# mapleSDuino-V0_1_020-eagle7.net
KiCad netlist of a schematic drawn in EAGLE
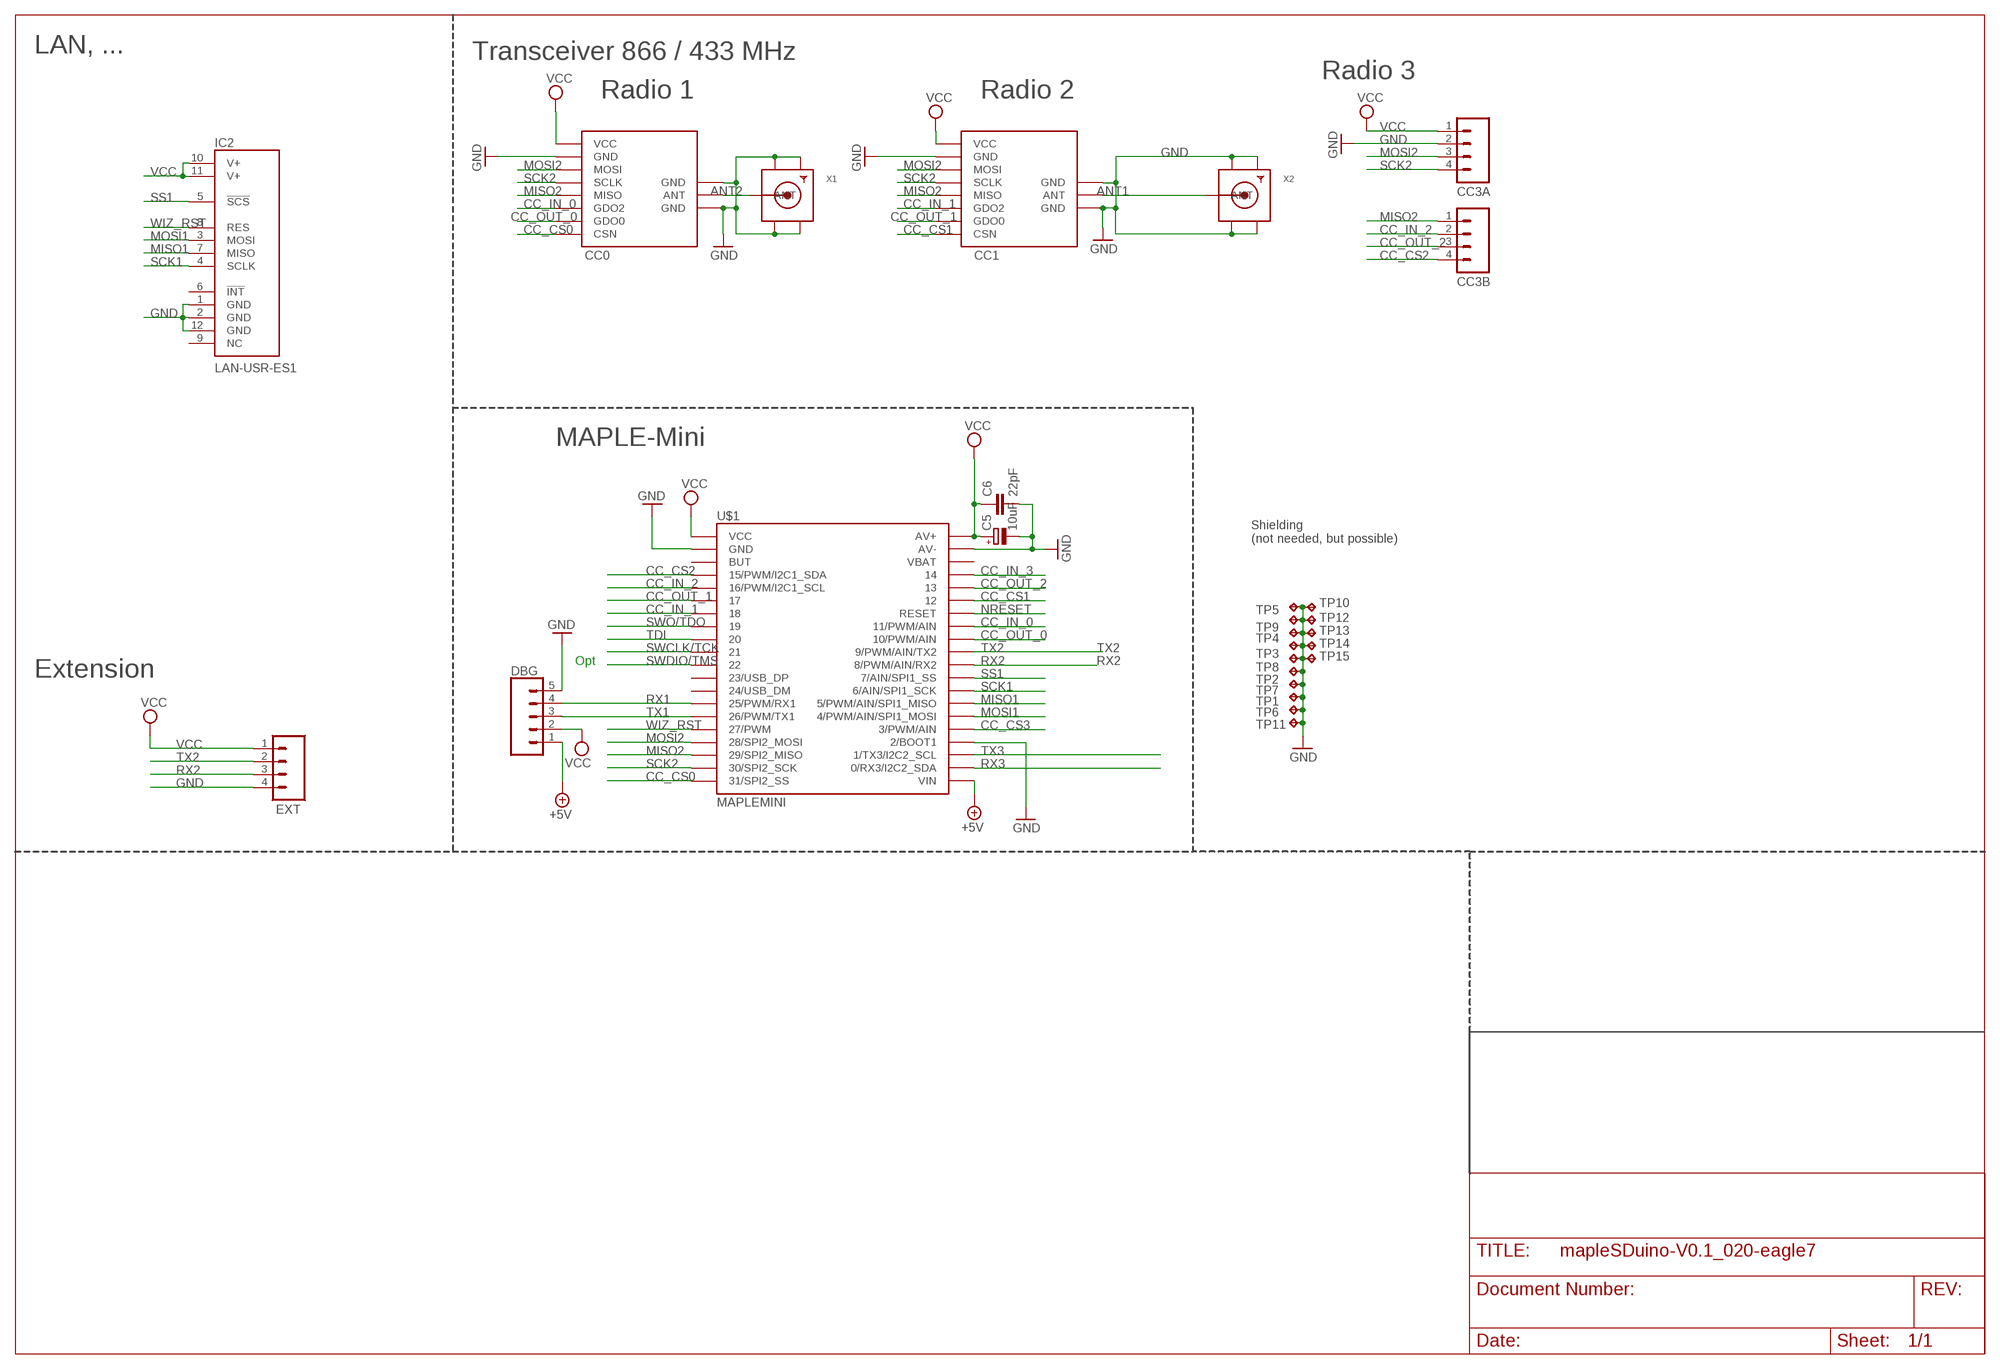
[diagram p0: schematic, sheet 1]

(export (version "E")
  (design (tool "Eeschema 10.0.6"))
  (components
    (comp (ref "C5")
      (value "10uF")
      (footprint "eagle-import:R_2012-12W")
      (libsource (lib "eagle-import") (part "CPOL-EUR/2012-12W"))
    )
    (comp (ref "C6")
      (value "22pF")
      (footprint "eagle-import:C0805")
      (libsource (lib "eagle-import") (part "C-EUC0805"))
    )
    (comp (ref "CC0")
      (value "CC1101")
      (footprint "eagle-import:CC1101_MODULE1_SMD")
      (libsource (lib "eagle-import") (part "CC1101_MODULE1SMD"))
    )
    (comp (ref "CC1")
      (value "CC1101_MODULE1SMD")
      (footprint "eagle-import:CC1101_MODULE1_SMD")
      (libsource (lib "eagle-import") (part "CC1101_MODULE1SMD"))
    )
    (comp (ref "CC3A")
      (value "CONN_04PTH")
      (footprint "eagle-import:1X04")
      (libsource (lib "eagle-import") (part "CONN_04PTH"))
    )
    (comp (ref "CC3B")
      (value "CONN_04PTH")
      (footprint "eagle-import:1X04")
      (libsource (lib "eagle-import") (part "CONN_04PTH"))
    )
    (comp (ref "DBG")
      (value "CONN_05LOCK")
      (footprint "eagle-import:1X05_LOCK")
      (libsource (lib "eagle-import") (part "CONN_05LOCK"))
    )
    (comp (ref "EXT")
      (value "CONN_04PTH")
      (footprint "eagle-import:1X04")
      (libsource (lib "eagle-import") (part "CONN_04PTH"))
    )
    (comp (ref "IC2")
      (value "LAN-USR-ES1")
      (footprint "eagle-import:USR-ES1")
      (libsource (lib "eagle-import") (part "LAN-USR-ES1"))
    )
    (comp (ref "TP1")
      (value "TPTP06SQ")
      (footprint "eagle-import:TP06SQ")
      (libsource (lib "eagle-import") (part "TPTP06SQ"))
    )
    (comp (ref "TP2")
      (value "TPTP06SQ")
      (footprint "eagle-import:TP06SQ")
      (libsource (lib "eagle-import") (part "TPTP06SQ"))
    )
    (comp (ref "TP3")
      (value "TPTP06SQ")
      (footprint "eagle-import:TP06SQ")
      (libsource (lib "eagle-import") (part "TPTP06SQ"))
    )
    (comp (ref "TP4")
      (value "TPTP06SQ")
      (footprint "eagle-import:TP06SQ")
      (libsource (lib "eagle-import") (part "TPTP06SQ"))
    )
    (comp (ref "TP5")
      (value "TPTP06SQ")
      (footprint "eagle-import:TP06SQ")
      (libsource (lib "eagle-import") (part "TPTP06SQ"))
    )
    (comp (ref "TP6")
      (value "TPTP06SQ")
      (footprint "eagle-import:TP06SQ")
      (libsource (lib "eagle-import") (part "TPTP06SQ"))
    )
    (comp (ref "TP7")
      (value "TPTP06SQ")
      (footprint "eagle-import:TP06SQ")
      (libsource (lib "eagle-import") (part "TPTP06SQ"))
    )
    (comp (ref "TP8")
      (value "TPTP06SQ")
      (footprint "eagle-import:TP06SQ")
      (libsource (lib "eagle-import") (part "TPTP06SQ"))
    )
    (comp (ref "TP9")
      (value "TPTP06SQ")
      (footprint "eagle-import:TP06SQ")
      (libsource (lib "eagle-import") (part "TPTP06SQ"))
    )
    (comp (ref "TP10")
      (value "TPTP06SQ")
      (footprint "eagle-import:TP06SQ")
      (libsource (lib "eagle-import") (part "TPTP06SQ"))
    )
    (comp (ref "TP11")
      (value "TPTP06SQ")
      (footprint "eagle-import:TP06SQ")
      (libsource (lib "eagle-import") (part "TPTP06SQ"))
    )
    (comp (ref "TP12")
      (value "TPTP06SQ")
      (footprint "eagle-import:TP06SQ")
      (libsource (lib "eagle-import") (part "TPTP06SQ"))
    )
    (comp (ref "TP13")
      (value "TPTP06SQ")
      (footprint "eagle-import:TP06SQ")
      (libsource (lib "eagle-import") (part "TPTP06SQ"))
    )
    (comp (ref "TP14")
      (value "TPTP06SQ")
      (footprint "eagle-import:TP06SQ")
      (libsource (lib "eagle-import") (part "TPTP06SQ"))
    )
    (comp (ref "TP15")
      (value "TPTP06SQ")
      (footprint "eagle-import:TP06SQ")
      (libsource (lib "eagle-import") (part "TPTP06SQ"))
    )
    (comp (ref "U$1")
      (value "MAPLEMINI")
      (footprint "eagle-import:20-DIP")
      (libsource (lib "eagle-import") (part "MAPLEMINI"))
    )
    (comp (ref "X1")
      (value "SMACONNECTOR_EDGE")
      (footprint "eagle-import:SMA_EDGELAUNCH")
      (libsource (lib "eagle-import") (part "SMACONNECTOR_EDGE"))
    )
    (comp (ref "X2")
      (value "SMACONNECTOR_EDGE")
      (footprint "eagle-import:SMA_EDGELAUNCH")
      (libsource (lib "eagle-import") (part "SMACONNECTOR_EDGE"))
    )
  )
  (nets
    (net (code "1") (name "+5V") (class "Default")
      (node (ref "DBG") (pin "1") (pinfunction "1_1") (pintype "passive"))
      (node (ref "U$1") (pin "21") (pinfunction "VIN_21") (pintype "bidirectional"))
    )
    (net (code "2") (name "/ANT1") (class "Default")
      (node (ref "CC1") (pin "ANT") (pinfunction "ANT_ANT") (pintype "output"))
      (node (ref "X2") (pin "P") (pinfunction "ANT_P") (pintype "bidirectional"))
    )
    (net (code "3") (name "/ANT2") (class "Default")
      (node (ref "CC0") (pin "ANT") (pinfunction "ANT_ANT") (pintype "output"))
      (node (ref "X1") (pin "P") (pinfunction "ANT_P") (pintype "bidirectional"))
    )
    (net (code "4") (name "/CC_CS0") (class "Default")
      (node (ref "CC0") (pin "CSN") (pinfunction "CSN_CSN") (pintype "bidirectional"))
      (node (ref "U$1") (pin "20") (pinfunction "31/SPI2_SS_20") (pintype "bidirectional"))
    )
    (net (code "5") (name "/CC_CS1") (class "Default")
      (node (ref "CC1") (pin "CSN") (pinfunction "CSN_CSN") (pintype "bidirectional"))
      (node (ref "U$1") (pin "35") (pinfunction "12_35") (pintype "bidirectional"))
    )
    (net (code "6") (name "/CC_CS2") (class "Default")
      (node (ref "CC3B") (pin "4") (pinfunction "4_4") (pintype "passive"))
      (node (ref "U$1") (pin "4") (pinfunction "15/PWM/I2C1_SDA_4") (pintype "bidirectional"))
    )
    (net (code "7") (name "/CC_CS3") (class "Default")
      (node (ref "U$1") (pin "25") (pinfunction "3/PWM/AIN_25") (pintype "bidirectional"))
    )
    (net (code "8") (name "/CC_IN_0") (class "Default")
      (node (ref "CC0") (pin "GDO2") (pinfunction "GDO2_GDO2") (pintype "bidirectional"))
      (node (ref "U$1") (pin "33") (pinfunction "11/PWM/AIN_33") (pintype "bidirectional"))
    )
    (net (code "9") (name "/CC_IN_1") (class "Default")
      (node (ref "CC1") (pin "GDO2") (pinfunction "GDO2_GDO2") (pintype "bidirectional"))
      (node (ref "U$1") (pin "7") (pinfunction "18_7") (pintype "bidirectional"))
    )
    (net (code "10") (name "/CC_IN_2") (class "Default")
      (node (ref "CC3B") (pin "2") (pinfunction "2_2") (pintype "passive"))
      (node (ref "U$1") (pin "5") (pinfunction "16/PWM/I2C1_SCL_5") (pintype "bidirectional"))
    )
    (net (code "11") (name "/CC_IN_3") (class "Default")
      (node (ref "U$1") (pin "37") (pinfunction "14_37") (pintype "bidirectional"))
    )
    (net (code "12") (name "/CC_OUT_0") (class "Default")
      (node (ref "CC0") (pin "GDO0") (pinfunction "GDO0_GDO0") (pintype "bidirectional"))
      (node (ref "U$1") (pin "32") (pinfunction "10/PWM/AIN_32") (pintype "bidirectional"))
    )
    (net (code "13") (name "/CC_OUT_1") (class "Default")
      (node (ref "CC1") (pin "GDO0") (pinfunction "GDO0_GDO0") (pintype "bidirectional"))
      (node (ref "U$1") (pin "6") (pinfunction "17_6") (pintype "bidirectional"))
    )
    (net (code "14") (name "/CC_OUT_2") (class "Default")
      (node (ref "CC3B") (pin "3") (pinfunction "3_3") (pintype "passive"))
      (node (ref "U$1") (pin "36") (pinfunction "13_36") (pintype "bidirectional"))
    )
    (net (code "15") (name "/MISO1") (class "Default")
      (node (ref "IC2") (pin "7") (pinfunction "MISO_7") (pintype "bidirectional"))
      (node (ref "U$1") (pin "27") (pinfunction "5/PWM/AIN/SPI1_MISO_27") (pintype "bidirectional"))
    )
    (net (code "16") (name "/MISO2") (class "Default")
      (node (ref "CC0") (pin "MISO") (pinfunction "MISO_MISO") (pintype "bidirectional"))
      (node (ref "CC1") (pin "MISO") (pinfunction "MISO_MISO") (pintype "bidirectional"))
      (node (ref "CC3B") (pin "1") (pinfunction "1_1") (pintype "passive"))
      (node (ref "U$1") (pin "18") (pinfunction "29/SPI2_MISO_18") (pintype "bidirectional"))
    )
    (net (code "17") (name "/MOSI1") (class "Default")
      (node (ref "IC2") (pin "3") (pinfunction "MOSI_3") (pintype "bidirectional"))
      (node (ref "U$1") (pin "26") (pinfunction "4/PWM/AIN/SPI1_MOSI_26") (pintype "bidirectional"))
    )
    (net (code "18") (name "/MOSI2") (class "Default")
      (node (ref "CC0") (pin "MOSI") (pinfunction "MOSI_MOSI") (pintype "bidirectional"))
      (node (ref "CC1") (pin "MOSI") (pinfunction "MOSI_MOSI") (pintype "bidirectional"))
      (node (ref "CC3A") (pin "3") (pinfunction "3_3") (pintype "passive"))
      (node (ref "U$1") (pin "17") (pinfunction "28/SPI2_MOSI_17") (pintype "bidirectional"))
    )
    (net (code "19") (name "/NRESET") (class "Default")
      (node (ref "U$1") (pin "34") (pinfunction "RESET_34") (pintype "bidirectional"))
    )
    (net (code "20") (name "/RX1") (class "Default")
      (node (ref "DBG") (pin "4") (pinfunction "4_4") (pintype "passive"))
      (node (ref "U$1") (pin "14") (pinfunction "25/PWM/RX1_14") (pintype "bidirectional"))
    )
    (net (code "21") (name "/RX2") (class "Default")
      (node (ref "EXT") (pin "3") (pinfunction "3_3") (pintype "passive"))
      (node (ref "U$1") (pin "30") (pinfunction "8/PWM/AIN/RX2_30") (pintype "bidirectional"))
    )
    (net (code "22") (name "/RX3") (class "Default")
      (node (ref "U$1") (pin "22") (pinfunction "0/RX3/I2C2_SDA_22") (pintype "bidirectional"))
    )
    (net (code "23") (name "/SCK1") (class "Default")
      (node (ref "IC2") (pin "4") (pinfunction "SCLK_4") (pintype "input"))
      (node (ref "U$1") (pin "28") (pinfunction "6/AIN/SPI1_SCK_28") (pintype "bidirectional"))
    )
    (net (code "24") (name "/SCK2") (class "Default")
      (node (ref "CC0") (pin "SCLK") (pinfunction "SCLK_SCLK") (pintype "bidirectional"))
      (node (ref "CC1") (pin "SCLK") (pinfunction "SCLK_SCLK") (pintype "bidirectional"))
      (node (ref "CC3A") (pin "4") (pinfunction "4_4") (pintype "passive"))
      (node (ref "U$1") (pin "19") (pinfunction "30/SPI2_SCK_19") (pintype "bidirectional"))
    )
    (net (code "25") (name "/SS1") (class "Default")
      (node (ref "IC2") (pin "5") (pinfunction "~{SCS}_5") (pintype "input"))
      (node (ref "U$1") (pin "29") (pinfunction "7/AIN/SPI1_SS_29") (pintype "bidirectional"))
    )
    (net (code "26") (name "/SWCLK{slash}TCK") (class "Default")
      (node (ref "U$1") (pin "10") (pinfunction "21_10") (pintype "bidirectional"))
    )
    (net (code "27") (name "/SWDIO{slash}TMS") (class "Default")
      (node (ref "U$1") (pin "11") (pinfunction "22_11") (pintype "bidirectional"))
    )
    (net (code "28") (name "/SWO{slash}TDO") (class "Default")
      (node (ref "U$1") (pin "8") (pinfunction "19_8") (pintype "bidirectional"))
    )
    (net (code "29") (name "/TDI") (class "Default")
      (node (ref "U$1") (pin "9") (pinfunction "20_9") (pintype "bidirectional"))
    )
    (net (code "30") (name "/TX1") (class "Default")
      (node (ref "DBG") (pin "3") (pinfunction "3_3") (pintype "passive"))
      (node (ref "U$1") (pin "15") (pinfunction "26/PWM/TX1_15") (pintype "bidirectional"))
    )
    (net (code "31") (name "/TX2") (class "Default")
      (node (ref "EXT") (pin "2") (pinfunction "2_2") (pintype "passive"))
      (node (ref "U$1") (pin "31") (pinfunction "9/PWM/AIN/TX2_31") (pintype "bidirectional"))
    )
    (net (code "32") (name "/TX3") (class "Default")
      (node (ref "U$1") (pin "23") (pinfunction "1/TX3/I2C2_SCL_23") (pintype "bidirectional"))
    )
    (net (code "33") (name "/WIZ_RST") (class "Default")
      (node (ref "IC2") (pin "8") (pinfunction "RES_8") (pintype "input"))
      (node (ref "U$1") (pin "16") (pinfunction "27/PWM_16") (pintype "bidirectional"))
    )
    (net (code "34") (name "GND") (class "Default")
      (node (ref "C5") (pin "-") (pinfunction "-_-") (pintype "passive"))
      (node (ref "C6") (pin "2") (pinfunction "2_2") (pintype "passive"))
      (node (ref "CC0") (pin "GND@0") (pinfunction "GND_GND@0") (pintype "power_in"))
      (node (ref "CC0") (pin "GND@1") (pinfunction "GND_GND@1") (pintype "power_in"))
      (node (ref "CC0") (pin "GND@2") (pinfunction "GND_GND@2") (pintype "power_in"))
      (node (ref "CC1") (pin "GND@0") (pinfunction "GND_GND@0") (pintype "power_in"))
      (node (ref "CC1") (pin "GND@1") (pinfunction "GND_GND@1") (pintype "power_in"))
      (node (ref "CC1") (pin "GND@2") (pinfunction "GND_GND@2") (pintype "power_in"))
      (node (ref "CC3A") (pin "2") (pinfunction "2_2") (pintype "passive"))
      (node (ref "DBG") (pin "5") (pinfunction "5_5") (pintype "passive"))
      (node (ref "EXT") (pin "4") (pinfunction "4_4") (pintype "passive"))
      (node (ref "IC2") (pin "1") (pinfunction "GND_1") (pintype "power_in"))
      (node (ref "IC2") (pin "12") (pinfunction "GND_12") (pintype "power_in"))
      (node (ref "IC2") (pin "2") (pinfunction "GND_2") (pintype "power_in"))
      (node (ref "TP1") (pin "TP") (pinfunction "TP_TP") (pintype "input"))
      (node (ref "TP10") (pin "TP") (pinfunction "TP_TP") (pintype "input"))
      (node (ref "TP11") (pin "TP") (pinfunction "TP_TP") (pintype "input"))
      (node (ref "TP12") (pin "TP") (pinfunction "TP_TP") (pintype "input"))
      (node (ref "TP13") (pin "TP") (pinfunction "TP_TP") (pintype "input"))
      (node (ref "TP14") (pin "TP") (pinfunction "TP_TP") (pintype "input"))
      (node (ref "TP15") (pin "TP") (pinfunction "TP_TP") (pintype "input"))
      (node (ref "TP2") (pin "TP") (pinfunction "TP_TP") (pintype "input"))
      (node (ref "TP3") (pin "TP") (pinfunction "TP_TP") (pintype "input"))
      (node (ref "TP4") (pin "TP") (pinfunction "TP_TP") (pintype "input"))
      (node (ref "TP5") (pin "TP") (pinfunction "TP_TP") (pintype "input"))
      (node (ref "TP6") (pin "TP") (pinfunction "TP_TP") (pintype "input"))
      (node (ref "TP7") (pin "TP") (pinfunction "TP_TP") (pintype "input"))
      (node (ref "TP8") (pin "TP") (pinfunction "TP_TP") (pintype "input"))
      (node (ref "TP9") (pin "TP") (pinfunction "TP_TP") (pintype "input"))
      (node (ref "U$1") (pin "2") (pinfunction "GND_2") (pintype "bidirectional"))
      (node (ref "U$1") (pin "24") (pinfunction "2/BOOT1_24") (pintype "bidirectional"))
      (node (ref "U$1") (pin "39") (pinfunction "AV-_39") (pintype "bidirectional"))
      (node (ref "X1") (pin "GND@1") (pinfunction "GND4_GND@1") (pintype "power_in"))
      (node (ref "X1") (pin "GND@2") (pinfunction "GND3_GND@2") (pintype "power_in"))
      (node (ref "X1") (pin "GND@3") (pinfunction "GND2_GND@3") (pintype "power_in"))
      (node (ref "X1") (pin "GND@4") (pinfunction "GND1_GND@4") (pintype "power_in"))
      (node (ref "X2") (pin "GND@1") (pinfunction "GND4_GND@1") (pintype "power_in"))
      (node (ref "X2") (pin "GND@2") (pinfunction "GND3_GND@2") (pintype "power_in"))
      (node (ref "X2") (pin "GND@3") (pinfunction "GND2_GND@3") (pintype "power_in"))
      (node (ref "X2") (pin "GND@4") (pinfunction "GND1_GND@4") (pintype "power_in"))
    )
    (net (code "35") (name "VCC") (class "Default")
      (node (ref "C5") (pin "+") (pinfunction "+_+") (pintype "passive"))
      (node (ref "C6") (pin "1") (pinfunction "1_1") (pintype "passive"))
      (node (ref "CC0") (pin "VCC") (pinfunction "VCC_VCC") (pintype "power_in"))
      (node (ref "CC1") (pin "VCC") (pinfunction "VCC_VCC") (pintype "power_in"))
      (node (ref "CC3A") (pin "1") (pinfunction "1_1") (pintype "passive"))
      (node (ref "DBG") (pin "2") (pinfunction "2_2") (pintype "passive"))
      (node (ref "EXT") (pin "1") (pinfunction "1_1") (pintype "passive"))
      (node (ref "IC2") (pin "10") (pinfunction "V+_10") (pintype "power_in"))
      (node (ref "IC2") (pin "11") (pinfunction "V+_11") (pintype "power_in"))
      (node (ref "U$1") (pin "1") (pinfunction "VCC_1") (pintype "bidirectional"))
      (node (ref "U$1") (pin "40") (pinfunction "AV+_40") (pintype "bidirectional"))
    )
    (net (code "36") (name "unconnected-(IC2-NC-Pad9)") (class "Default")
      (node (ref "IC2") (pin "9") (pinfunction "NC_9") (pintype "no_connect"))
    )
    (net (code "37") (name "unconnected-(IC2-~{INT}-Pad6)") (class "Default")
      (node (ref "IC2") (pin "6") (pinfunction "~{INT}_6") (pintype "output"))
    )
    (net (code "38") (name "unconnected-(U$1-23{slash}USB_DP-Pad12)") (class "Default")
      (node (ref "U$1") (pin "12") (pinfunction "23/USB_DP_12") (pintype "bidirectional"))
    )
    (net (code "39") (name "unconnected-(U$1-24{slash}USB_DM-Pad13)") (class "Default")
      (node (ref "U$1") (pin "13") (pinfunction "24/USB_DM_13") (pintype "bidirectional"))
    )
    (net (code "40") (name "unconnected-(U$1-BUT-Pad3)") (class "Default")
      (node (ref "U$1") (pin "3") (pinfunction "BUT_3") (pintype "bidirectional"))
    )
    (net (code "41") (name "unconnected-(U$1-VBAT-Pad38)") (class "Default")
      (node (ref "U$1") (pin "38") (pinfunction "VBAT_38") (pintype "bidirectional"))
    )
  )
)
